# martix_connect_2.net
KiCad netlist of a schematic drawn in Altium Designer
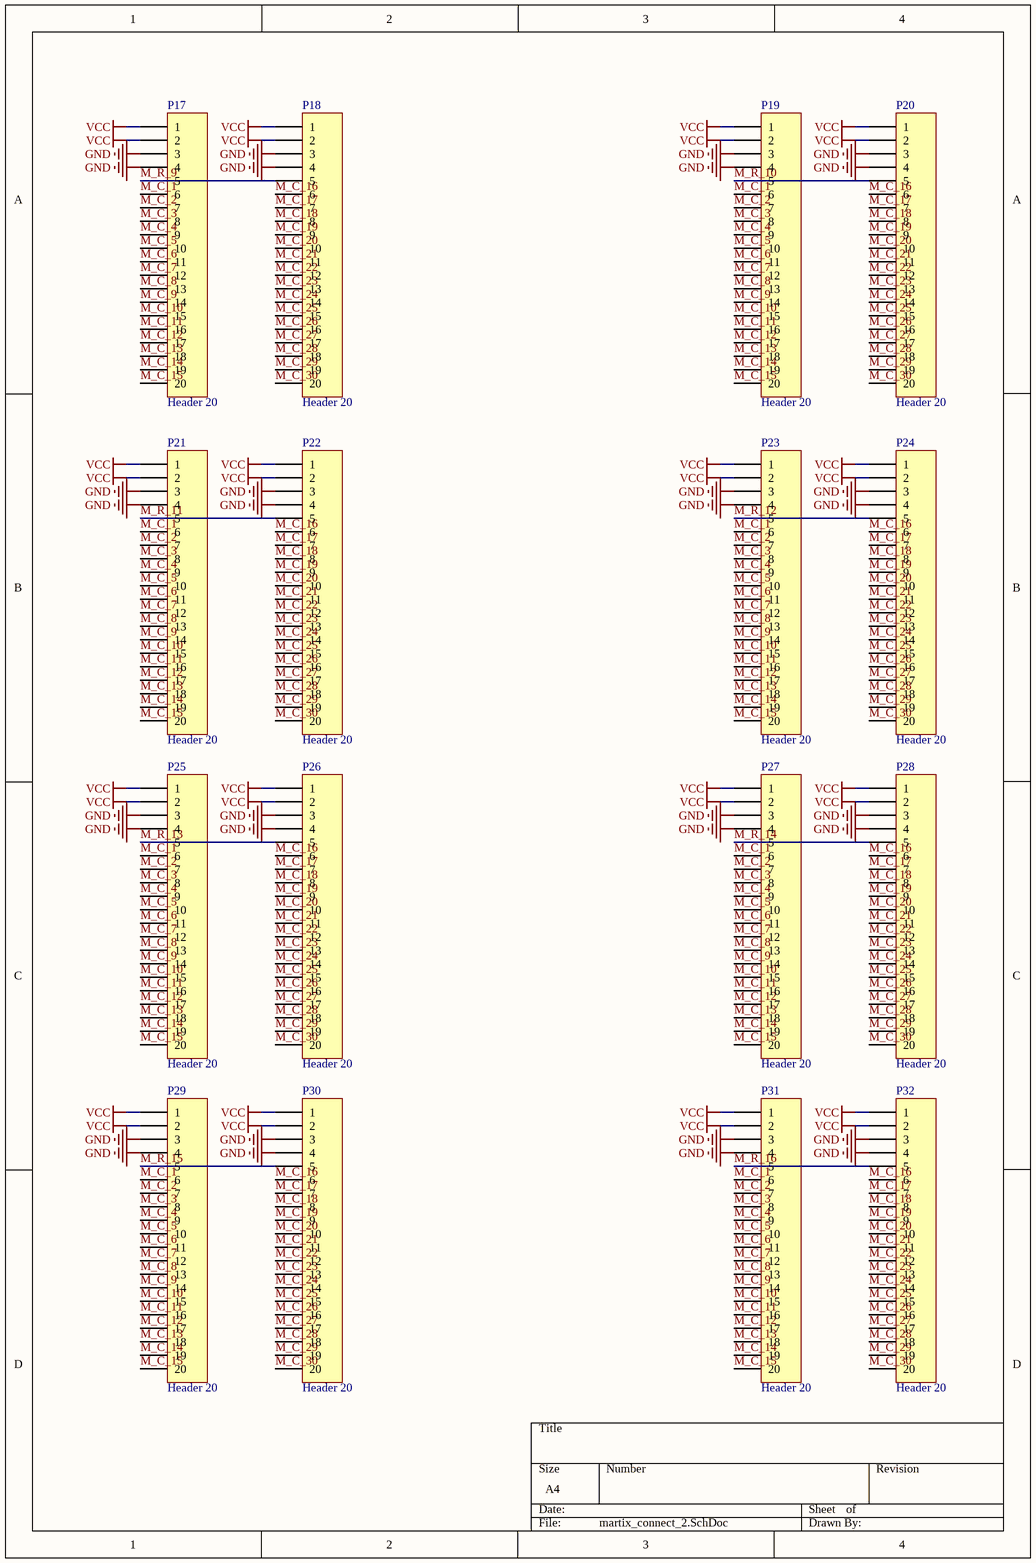
[diagram p0: martix_connect_2.SchDoc]

(export (version "E")
  (design (tool "Eeschema 10.0.6"))
  (components
    (comp (ref "P17")
      (value "Header 20")
      (footprint "FPC0.5 2H-WS-20P")
      (description "Header, 20-Pin")
      (fields (field (name "PUBLISHER") "Altium Limited"))
      (libsource (lib "Miscellaneous Connectors") (part "Header 20"))
    )
    (comp (ref "P18")
      (value "Header 20")
      (footprint "FPC0.5 2H-WS-20P")
      (description "Header, 20-Pin")
      (fields (field (name "PUBLISHER") "Altium Limited"))
      (libsource (lib "Miscellaneous Connectors") (part "Header 20"))
    )
    (comp (ref "P19")
      (value "Header 20")
      (footprint "FPC0.5 2H-WS-20P")
      (description "Header, 20-Pin")
      (fields (field (name "PUBLISHER") "Altium Limited"))
      (libsource (lib "Miscellaneous Connectors") (part "Header 20"))
    )
    (comp (ref "P20")
      (value "Header 20")
      (footprint "FPC0.5 2H-WS-20P")
      (description "Header, 20-Pin")
      (fields (field (name "PUBLISHER") "Altium Limited"))
      (libsource (lib "Miscellaneous Connectors") (part "Header 20"))
    )
    (comp (ref "P21")
      (value "Header 20")
      (footprint "FPC0.5 2H-WS-20P")
      (description "Header, 20-Pin")
      (fields (field (name "PUBLISHER") "Altium Limited"))
      (libsource (lib "Miscellaneous Connectors") (part "Header 20"))
    )
    (comp (ref "P22")
      (value "Header 20")
      (footprint "FPC0.5 2H-WS-20P")
      (description "Header, 20-Pin")
      (fields (field (name "PUBLISHER") "Altium Limited"))
      (libsource (lib "Miscellaneous Connectors") (part "Header 20"))
    )
    (comp (ref "P23")
      (value "Header 20")
      (footprint "FPC0.5 2H-WS-20P")
      (description "Header, 20-Pin")
      (fields (field (name "PUBLISHER") "Altium Limited"))
      (libsource (lib "Miscellaneous Connectors") (part "Header 20"))
    )
    (comp (ref "P24")
      (value "Header 20")
      (footprint "FPC0.5 2H-WS-20P")
      (description "Header, 20-Pin")
      (fields (field (name "PUBLISHER") "Altium Limited"))
      (libsource (lib "Miscellaneous Connectors") (part "Header 20"))
    )
    (comp (ref "P25")
      (value "Header 20")
      (footprint "FPC0.5 2H-WS-20P")
      (description "Header, 20-Pin")
      (fields (field (name "PUBLISHER") "Altium Limited"))
      (libsource (lib "Miscellaneous Connectors") (part "Header 20"))
    )
    (comp (ref "P26")
      (value "Header 20")
      (footprint "FPC0.5 2H-WS-20P")
      (description "Header, 20-Pin")
      (fields (field (name "PUBLISHER") "Altium Limited"))
      (libsource (lib "Miscellaneous Connectors") (part "Header 20"))
    )
    (comp (ref "P27")
      (value "Header 20")
      (footprint "FPC0.5 2H-WS-20P")
      (description "Header, 20-Pin")
      (fields (field (name "PUBLISHER") "Altium Limited"))
      (libsource (lib "Miscellaneous Connectors") (part "Header 20"))
    )
    (comp (ref "P28")
      (value "Header 20")
      (footprint "FPC0.5 2H-WS-20P")
      (description "Header, 20-Pin")
      (fields (field (name "PUBLISHER") "Altium Limited"))
      (libsource (lib "Miscellaneous Connectors") (part "Header 20"))
    )
    (comp (ref "P29")
      (value "Header 20")
      (footprint "FPC0.5 2H-WS-20P")
      (description "Header, 20-Pin")
      (fields (field (name "PUBLISHER") "Altium Limited"))
      (libsource (lib "Miscellaneous Connectors") (part "Header 20"))
    )
    (comp (ref "P30")
      (value "Header 20")
      (footprint "FPC0.5 2H-WS-20P")
      (description "Header, 20-Pin")
      (fields (field (name "PUBLISHER") "Altium Limited"))
      (libsource (lib "Miscellaneous Connectors") (part "Header 20"))
    )
    (comp (ref "P31")
      (value "Header 20")
      (footprint "FPC0.5 2H-WS-20P")
      (description "Header, 20-Pin")
      (fields (field (name "PUBLISHER") "Altium Limited"))
      (libsource (lib "Miscellaneous Connectors") (part "Header 20"))
    )
    (comp (ref "P32")
      (value "Header 20")
      (footprint "FPC0.5 2H-WS-20P")
      (description "Header, 20-Pin")
      (fields (field (name "PUBLISHER") "Altium Limited"))
      (libsource (lib "Miscellaneous Connectors") (part "Header 20"))
    )
  )
  (nets
    (net (code "1") (name "/M_C_1") (class "Default")
      (node (ref "P17") (pin "6") (pinfunction "6_6") (pintype "passive"))
      (node (ref "P19") (pin "6") (pinfunction "6_6") (pintype "passive"))
      (node (ref "P21") (pin "6") (pinfunction "6_6") (pintype "passive"))
      (node (ref "P23") (pin "6") (pinfunction "6_6") (pintype "passive"))
      (node (ref "P25") (pin "6") (pinfunction "6_6") (pintype "passive"))
      (node (ref "P27") (pin "6") (pinfunction "6_6") (pintype "passive"))
      (node (ref "P29") (pin "6") (pinfunction "6_6") (pintype "passive"))
      (node (ref "P31") (pin "6") (pinfunction "6_6") (pintype "passive"))
    )
    (net (code "2") (name "/M_C_2") (class "Default")
      (node (ref "P17") (pin "7") (pinfunction "7_7") (pintype "passive"))
      (node (ref "P19") (pin "7") (pinfunction "7_7") (pintype "passive"))
      (node (ref "P21") (pin "7") (pinfunction "7_7") (pintype "passive"))
      (node (ref "P23") (pin "7") (pinfunction "7_7") (pintype "passive"))
      (node (ref "P25") (pin "7") (pinfunction "7_7") (pintype "passive"))
      (node (ref "P27") (pin "7") (pinfunction "7_7") (pintype "passive"))
      (node (ref "P29") (pin "7") (pinfunction "7_7") (pintype "passive"))
      (node (ref "P31") (pin "7") (pinfunction "7_7") (pintype "passive"))
    )
    (net (code "3") (name "/M_C_3") (class "Default")
      (node (ref "P17") (pin "8") (pinfunction "8_8") (pintype "passive"))
      (node (ref "P19") (pin "8") (pinfunction "8_8") (pintype "passive"))
      (node (ref "P21") (pin "8") (pinfunction "8_8") (pintype "passive"))
      (node (ref "P23") (pin "8") (pinfunction "8_8") (pintype "passive"))
      (node (ref "P25") (pin "8") (pinfunction "8_8") (pintype "passive"))
      (node (ref "P27") (pin "8") (pinfunction "8_8") (pintype "passive"))
      (node (ref "P29") (pin "8") (pinfunction "8_8") (pintype "passive"))
      (node (ref "P31") (pin "8") (pinfunction "8_8") (pintype "passive"))
    )
    (net (code "4") (name "/M_C_4") (class "Default")
      (node (ref "P17") (pin "9") (pinfunction "9_9") (pintype "passive"))
      (node (ref "P19") (pin "9") (pinfunction "9_9") (pintype "passive"))
      (node (ref "P21") (pin "9") (pinfunction "9_9") (pintype "passive"))
      (node (ref "P23") (pin "9") (pinfunction "9_9") (pintype "passive"))
      (node (ref "P25") (pin "9") (pinfunction "9_9") (pintype "passive"))
      (node (ref "P27") (pin "9") (pinfunction "9_9") (pintype "passive"))
      (node (ref "P29") (pin "9") (pinfunction "9_9") (pintype "passive"))
      (node (ref "P31") (pin "9") (pinfunction "9_9") (pintype "passive"))
    )
    (net (code "5") (name "/M_C_5") (class "Default")
      (node (ref "P17") (pin "10") (pinfunction "10_10") (pintype "passive"))
      (node (ref "P19") (pin "10") (pinfunction "10_10") (pintype "passive"))
      (node (ref "P21") (pin "10") (pinfunction "10_10") (pintype "passive"))
      (node (ref "P23") (pin "10") (pinfunction "10_10") (pintype "passive"))
      (node (ref "P25") (pin "10") (pinfunction "10_10") (pintype "passive"))
      (node (ref "P27") (pin "10") (pinfunction "10_10") (pintype "passive"))
      (node (ref "P29") (pin "10") (pinfunction "10_10") (pintype "passive"))
      (node (ref "P31") (pin "10") (pinfunction "10_10") (pintype "passive"))
    )
    (net (code "6") (name "/M_C_6") (class "Default")
      (node (ref "P17") (pin "11") (pinfunction "11_11") (pintype "passive"))
      (node (ref "P19") (pin "11") (pinfunction "11_11") (pintype "passive"))
      (node (ref "P21") (pin "11") (pinfunction "11_11") (pintype "passive"))
      (node (ref "P23") (pin "11") (pinfunction "11_11") (pintype "passive"))
      (node (ref "P25") (pin "11") (pinfunction "11_11") (pintype "passive"))
      (node (ref "P27") (pin "11") (pinfunction "11_11") (pintype "passive"))
      (node (ref "P29") (pin "11") (pinfunction "11_11") (pintype "passive"))
      (node (ref "P31") (pin "11") (pinfunction "11_11") (pintype "passive"))
    )
    (net (code "7") (name "/M_C_7") (class "Default")
      (node (ref "P17") (pin "12") (pinfunction "12_12") (pintype "passive"))
      (node (ref "P19") (pin "12") (pinfunction "12_12") (pintype "passive"))
      (node (ref "P21") (pin "12") (pinfunction "12_12") (pintype "passive"))
      (node (ref "P23") (pin "12") (pinfunction "12_12") (pintype "passive"))
      (node (ref "P25") (pin "12") (pinfunction "12_12") (pintype "passive"))
      (node (ref "P27") (pin "12") (pinfunction "12_12") (pintype "passive"))
      (node (ref "P29") (pin "12") (pinfunction "12_12") (pintype "passive"))
      (node (ref "P31") (pin "12") (pinfunction "12_12") (pintype "passive"))
    )
    (net (code "8") (name "/M_C_8") (class "Default")
      (node (ref "P17") (pin "13") (pinfunction "13_13") (pintype "passive"))
      (node (ref "P19") (pin "13") (pinfunction "13_13") (pintype "passive"))
      (node (ref "P21") (pin "13") (pinfunction "13_13") (pintype "passive"))
      (node (ref "P23") (pin "13") (pinfunction "13_13") (pintype "passive"))
      (node (ref "P25") (pin "13") (pinfunction "13_13") (pintype "passive"))
      (node (ref "P27") (pin "13") (pinfunction "13_13") (pintype "passive"))
      (node (ref "P29") (pin "13") (pinfunction "13_13") (pintype "passive"))
      (node (ref "P31") (pin "13") (pinfunction "13_13") (pintype "passive"))
    )
    (net (code "9") (name "/M_C_9") (class "Default")
      (node (ref "P17") (pin "14") (pinfunction "14_14") (pintype "passive"))
      (node (ref "P19") (pin "14") (pinfunction "14_14") (pintype "passive"))
      (node (ref "P21") (pin "14") (pinfunction "14_14") (pintype "passive"))
      (node (ref "P23") (pin "14") (pinfunction "14_14") (pintype "passive"))
      (node (ref "P25") (pin "14") (pinfunction "14_14") (pintype "passive"))
      (node (ref "P27") (pin "14") (pinfunction "14_14") (pintype "passive"))
      (node (ref "P29") (pin "14") (pinfunction "14_14") (pintype "passive"))
      (node (ref "P31") (pin "14") (pinfunction "14_14") (pintype "passive"))
    )
    (net (code "10") (name "/M_C_10") (class "Default")
      (node (ref "P17") (pin "15") (pinfunction "15_15") (pintype "passive"))
      (node (ref "P19") (pin "15") (pinfunction "15_15") (pintype "passive"))
      (node (ref "P21") (pin "15") (pinfunction "15_15") (pintype "passive"))
      (node (ref "P23") (pin "15") (pinfunction "15_15") (pintype "passive"))
      (node (ref "P25") (pin "15") (pinfunction "15_15") (pintype "passive"))
      (node (ref "P27") (pin "15") (pinfunction "15_15") (pintype "passive"))
      (node (ref "P29") (pin "15") (pinfunction "15_15") (pintype "passive"))
      (node (ref "P31") (pin "15") (pinfunction "15_15") (pintype "passive"))
    )
    (net (code "11") (name "/M_C_11") (class "Default")
      (node (ref "P17") (pin "16") (pinfunction "16_16") (pintype "passive"))
      (node (ref "P19") (pin "16") (pinfunction "16_16") (pintype "passive"))
      (node (ref "P21") (pin "16") (pinfunction "16_16") (pintype "passive"))
      (node (ref "P23") (pin "16") (pinfunction "16_16") (pintype "passive"))
      (node (ref "P25") (pin "16") (pinfunction "16_16") (pintype "passive"))
      (node (ref "P27") (pin "16") (pinfunction "16_16") (pintype "passive"))
      (node (ref "P29") (pin "16") (pinfunction "16_16") (pintype "passive"))
      (node (ref "P31") (pin "16") (pinfunction "16_16") (pintype "passive"))
    )
    (net (code "12") (name "/M_C_12") (class "Default")
      (node (ref "P17") (pin "17") (pinfunction "17_17") (pintype "passive"))
      (node (ref "P19") (pin "17") (pinfunction "17_17") (pintype "passive"))
      (node (ref "P21") (pin "17") (pinfunction "17_17") (pintype "passive"))
      (node (ref "P23") (pin "17") (pinfunction "17_17") (pintype "passive"))
      (node (ref "P25") (pin "17") (pinfunction "17_17") (pintype "passive"))
      (node (ref "P27") (pin "17") (pinfunction "17_17") (pintype "passive"))
      (node (ref "P29") (pin "17") (pinfunction "17_17") (pintype "passive"))
      (node (ref "P31") (pin "17") (pinfunction "17_17") (pintype "passive"))
    )
    (net (code "13") (name "/M_C_13") (class "Default")
      (node (ref "P17") (pin "18") (pinfunction "18_18") (pintype "passive"))
      (node (ref "P19") (pin "18") (pinfunction "18_18") (pintype "passive"))
      (node (ref "P21") (pin "18") (pinfunction "18_18") (pintype "passive"))
      (node (ref "P23") (pin "18") (pinfunction "18_18") (pintype "passive"))
      (node (ref "P25") (pin "18") (pinfunction "18_18") (pintype "passive"))
      (node (ref "P27") (pin "18") (pinfunction "18_18") (pintype "passive"))
      (node (ref "P29") (pin "18") (pinfunction "18_18") (pintype "passive"))
      (node (ref "P31") (pin "18") (pinfunction "18_18") (pintype "passive"))
    )
    (net (code "14") (name "/M_C_14") (class "Default")
      (node (ref "P17") (pin "19") (pinfunction "19_19") (pintype "passive"))
      (node (ref "P19") (pin "19") (pinfunction "19_19") (pintype "passive"))
      (node (ref "P21") (pin "19") (pinfunction "19_19") (pintype "passive"))
      (node (ref "P23") (pin "19") (pinfunction "19_19") (pintype "passive"))
      (node (ref "P25") (pin "19") (pinfunction "19_19") (pintype "passive"))
      (node (ref "P27") (pin "19") (pinfunction "19_19") (pintype "passive"))
      (node (ref "P29") (pin "19") (pinfunction "19_19") (pintype "passive"))
      (node (ref "P31") (pin "19") (pinfunction "19_19") (pintype "passive"))
    )
    (net (code "15") (name "/M_C_15") (class "Default")
      (node (ref "P17") (pin "20") (pinfunction "20_20") (pintype "passive"))
      (node (ref "P19") (pin "20") (pinfunction "20_20") (pintype "passive"))
      (node (ref "P21") (pin "20") (pinfunction "20_20") (pintype "passive"))
      (node (ref "P23") (pin "20") (pinfunction "20_20") (pintype "passive"))
      (node (ref "P25") (pin "20") (pinfunction "20_20") (pintype "passive"))
      (node (ref "P27") (pin "20") (pinfunction "20_20") (pintype "passive"))
      (node (ref "P29") (pin "20") (pinfunction "20_20") (pintype "passive"))
      (node (ref "P31") (pin "20") (pinfunction "20_20") (pintype "passive"))
    )
    (net (code "16") (name "/M_C_16") (class "Default")
      (node (ref "P18") (pin "6") (pinfunction "6_6") (pintype "passive"))
      (node (ref "P20") (pin "6") (pinfunction "6_6") (pintype "passive"))
      (node (ref "P22") (pin "6") (pinfunction "6_6") (pintype "passive"))
      (node (ref "P24") (pin "6") (pinfunction "6_6") (pintype "passive"))
      (node (ref "P26") (pin "6") (pinfunction "6_6") (pintype "passive"))
      (node (ref "P28") (pin "6") (pinfunction "6_6") (pintype "passive"))
      (node (ref "P30") (pin "6") (pinfunction "6_6") (pintype "passive"))
      (node (ref "P32") (pin "6") (pinfunction "6_6") (pintype "passive"))
    )
    (net (code "17") (name "/M_C_17") (class "Default")
      (node (ref "P18") (pin "7") (pinfunction "7_7") (pintype "passive"))
      (node (ref "P20") (pin "7") (pinfunction "7_7") (pintype "passive"))
      (node (ref "P22") (pin "7") (pinfunction "7_7") (pintype "passive"))
      (node (ref "P24") (pin "7") (pinfunction "7_7") (pintype "passive"))
      (node (ref "P26") (pin "7") (pinfunction "7_7") (pintype "passive"))
      (node (ref "P28") (pin "7") (pinfunction "7_7") (pintype "passive"))
      (node (ref "P30") (pin "7") (pinfunction "7_7") (pintype "passive"))
      (node (ref "P32") (pin "7") (pinfunction "7_7") (pintype "passive"))
    )
    (net (code "18") (name "/M_C_18") (class "Default")
      (node (ref "P18") (pin "8") (pinfunction "8_8") (pintype "passive"))
      (node (ref "P20") (pin "8") (pinfunction "8_8") (pintype "passive"))
      (node (ref "P22") (pin "8") (pinfunction "8_8") (pintype "passive"))
      (node (ref "P24") (pin "8") (pinfunction "8_8") (pintype "passive"))
      (node (ref "P26") (pin "8") (pinfunction "8_8") (pintype "passive"))
      (node (ref "P28") (pin "8") (pinfunction "8_8") (pintype "passive"))
      (node (ref "P30") (pin "8") (pinfunction "8_8") (pintype "passive"))
      (node (ref "P32") (pin "8") (pinfunction "8_8") (pintype "passive"))
    )
    (net (code "19") (name "/M_C_19") (class "Default")
      (node (ref "P18") (pin "9") (pinfunction "9_9") (pintype "passive"))
      (node (ref "P20") (pin "9") (pinfunction "9_9") (pintype "passive"))
      (node (ref "P22") (pin "9") (pinfunction "9_9") (pintype "passive"))
      (node (ref "P24") (pin "9") (pinfunction "9_9") (pintype "passive"))
      (node (ref "P26") (pin "9") (pinfunction "9_9") (pintype "passive"))
      (node (ref "P28") (pin "9") (pinfunction "9_9") (pintype "passive"))
      (node (ref "P30") (pin "9") (pinfunction "9_9") (pintype "passive"))
      (node (ref "P32") (pin "9") (pinfunction "9_9") (pintype "passive"))
    )
    (net (code "20") (name "/M_C_20") (class "Default")
      (node (ref "P18") (pin "10") (pinfunction "10_10") (pintype "passive"))
      (node (ref "P20") (pin "10") (pinfunction "10_10") (pintype "passive"))
      (node (ref "P22") (pin "10") (pinfunction "10_10") (pintype "passive"))
      (node (ref "P24") (pin "10") (pinfunction "10_10") (pintype "passive"))
      (node (ref "P26") (pin "10") (pinfunction "10_10") (pintype "passive"))
      (node (ref "P28") (pin "10") (pinfunction "10_10") (pintype "passive"))
      (node (ref "P30") (pin "10") (pinfunction "10_10") (pintype "passive"))
      (node (ref "P32") (pin "10") (pinfunction "10_10") (pintype "passive"))
    )
    (net (code "21") (name "/M_C_21") (class "Default")
      (node (ref "P18") (pin "11") (pinfunction "11_11") (pintype "passive"))
      (node (ref "P20") (pin "11") (pinfunction "11_11") (pintype "passive"))
      (node (ref "P22") (pin "11") (pinfunction "11_11") (pintype "passive"))
      (node (ref "P24") (pin "11") (pinfunction "11_11") (pintype "passive"))
      (node (ref "P26") (pin "11") (pinfunction "11_11") (pintype "passive"))
      (node (ref "P28") (pin "11") (pinfunction "11_11") (pintype "passive"))
      (node (ref "P30") (pin "11") (pinfunction "11_11") (pintype "passive"))
      (node (ref "P32") (pin "11") (pinfunction "11_11") (pintype "passive"))
    )
    (net (code "22") (name "/M_C_22") (class "Default")
      (node (ref "P18") (pin "12") (pinfunction "12_12") (pintype "passive"))
      (node (ref "P20") (pin "12") (pinfunction "12_12") (pintype "passive"))
      (node (ref "P22") (pin "12") (pinfunction "12_12") (pintype "passive"))
      (node (ref "P24") (pin "12") (pinfunction "12_12") (pintype "passive"))
      (node (ref "P26") (pin "12") (pinfunction "12_12") (pintype "passive"))
      (node (ref "P28") (pin "12") (pinfunction "12_12") (pintype "passive"))
      (node (ref "P30") (pin "12") (pinfunction "12_12") (pintype "passive"))
      (node (ref "P32") (pin "12") (pinfunction "12_12") (pintype "passive"))
    )
    (net (code "23") (name "/M_C_23") (class "Default")
      (node (ref "P18") (pin "13") (pinfunction "13_13") (pintype "passive"))
      (node (ref "P20") (pin "13") (pinfunction "13_13") (pintype "passive"))
      (node (ref "P22") (pin "13") (pinfunction "13_13") (pintype "passive"))
      (node (ref "P24") (pin "13") (pinfunction "13_13") (pintype "passive"))
      (node (ref "P26") (pin "13") (pinfunction "13_13") (pintype "passive"))
      (node (ref "P28") (pin "13") (pinfunction "13_13") (pintype "passive"))
      (node (ref "P30") (pin "13") (pinfunction "13_13") (pintype "passive"))
      (node (ref "P32") (pin "13") (pinfunction "13_13") (pintype "passive"))
    )
    (net (code "24") (name "/M_C_24") (class "Default")
      (node (ref "P18") (pin "14") (pinfunction "14_14") (pintype "passive"))
      (node (ref "P20") (pin "14") (pinfunction "14_14") (pintype "passive"))
      (node (ref "P22") (pin "14") (pinfunction "14_14") (pintype "passive"))
      (node (ref "P24") (pin "14") (pinfunction "14_14") (pintype "passive"))
      (node (ref "P26") (pin "14") (pinfunction "14_14") (pintype "passive"))
      (node (ref "P28") (pin "14") (pinfunction "14_14") (pintype "passive"))
      (node (ref "P30") (pin "14") (pinfunction "14_14") (pintype "passive"))
      (node (ref "P32") (pin "14") (pinfunction "14_14") (pintype "passive"))
    )
    (net (code "25") (name "/M_C_25") (class "Default")
      (node (ref "P18") (pin "15") (pinfunction "15_15") (pintype "passive"))
      (node (ref "P20") (pin "15") (pinfunction "15_15") (pintype "passive"))
      (node (ref "P22") (pin "15") (pinfunction "15_15") (pintype "passive"))
      (node (ref "P24") (pin "15") (pinfunction "15_15") (pintype "passive"))
      (node (ref "P26") (pin "15") (pinfunction "15_15") (pintype "passive"))
      (node (ref "P28") (pin "15") (pinfunction "15_15") (pintype "passive"))
      (node (ref "P30") (pin "15") (pinfunction "15_15") (pintype "passive"))
      (node (ref "P32") (pin "15") (pinfunction "15_15") (pintype "passive"))
    )
    (net (code "26") (name "/M_C_26") (class "Default")
      (node (ref "P18") (pin "16") (pinfunction "16_16") (pintype "passive"))
      (node (ref "P20") (pin "16") (pinfunction "16_16") (pintype "passive"))
      (node (ref "P22") (pin "16") (pinfunction "16_16") (pintype "passive"))
      (node (ref "P24") (pin "16") (pinfunction "16_16") (pintype "passive"))
      (node (ref "P26") (pin "16") (pinfunction "16_16") (pintype "passive"))
      (node (ref "P28") (pin "16") (pinfunction "16_16") (pintype "passive"))
      (node (ref "P30") (pin "16") (pinfunction "16_16") (pintype "passive"))
      (node (ref "P32") (pin "16") (pinfunction "16_16") (pintype "passive"))
    )
    (net (code "27") (name "/M_C_27") (class "Default")
      (node (ref "P18") (pin "17") (pinfunction "17_17") (pintype "passive"))
      (node (ref "P20") (pin "17") (pinfunction "17_17") (pintype "passive"))
      (node (ref "P22") (pin "17") (pinfunction "17_17") (pintype "passive"))
      (node (ref "P24") (pin "17") (pinfunction "17_17") (pintype "passive"))
      (node (ref "P26") (pin "17") (pinfunction "17_17") (pintype "passive"))
      (node (ref "P28") (pin "17") (pinfunction "17_17") (pintype "passive"))
      (node (ref "P30") (pin "17") (pinfunction "17_17") (pintype "passive"))
      (node (ref "P32") (pin "17") (pinfunction "17_17") (pintype "passive"))
    )
    (net (code "28") (name "/M_C_28") (class "Default")
      (node (ref "P18") (pin "18") (pinfunction "18_18") (pintype "passive"))
      (node (ref "P20") (pin "18") (pinfunction "18_18") (pintype "passive"))
      (node (ref "P22") (pin "18") (pinfunction "18_18") (pintype "passive"))
      (node (ref "P24") (pin "18") (pinfunction "18_18") (pintype "passive"))
      (node (ref "P26") (pin "18") (pinfunction "18_18") (pintype "passive"))
      (node (ref "P28") (pin "18") (pinfunction "18_18") (pintype "passive"))
      (node (ref "P30") (pin "18") (pinfunction "18_18") (pintype "passive"))
      (node (ref "P32") (pin "18") (pinfunction "18_18") (pintype "passive"))
    )
    (net (code "29") (name "/M_C_29") (class "Default")
      (node (ref "P18") (pin "19") (pinfunction "19_19") (pintype "passive"))
      (node (ref "P20") (pin "19") (pinfunction "19_19") (pintype "passive"))
      (node (ref "P22") (pin "19") (pinfunction "19_19") (pintype "passive"))
      (node (ref "P24") (pin "19") (pinfunction "19_19") (pintype "passive"))
      (node (ref "P26") (pin "19") (pinfunction "19_19") (pintype "passive"))
      (node (ref "P28") (pin "19") (pinfunction "19_19") (pintype "passive"))
      (node (ref "P30") (pin "19") (pinfunction "19_19") (pintype "passive"))
      (node (ref "P32") (pin "19") (pinfunction "19_19") (pintype "passive"))
    )
    (net (code "30") (name "/M_C_30") (class "Default")
      (node (ref "P18") (pin "20") (pinfunction "20_20") (pintype "passive"))
      (node (ref "P20") (pin "20") (pinfunction "20_20") (pintype "passive"))
      (node (ref "P22") (pin "20") (pinfunction "20_20") (pintype "passive"))
      (node (ref "P24") (pin "20") (pinfunction "20_20") (pintype "passive"))
      (node (ref "P26") (pin "20") (pinfunction "20_20") (pintype "passive"))
      (node (ref "P28") (pin "20") (pinfunction "20_20") (pintype "passive"))
      (node (ref "P30") (pin "20") (pinfunction "20_20") (pintype "passive"))
      (node (ref "P32") (pin "20") (pinfunction "20_20") (pintype "passive"))
    )
    (net (code "31") (name "/M_R_9") (class "Default")
      (node (ref "P17") (pin "5") (pinfunction "5_5") (pintype "passive"))
      (node (ref "P18") (pin "5") (pinfunction "5_5") (pintype "passive"))
    )
    (net (code "32") (name "/M_R_10") (class "Default")
      (node (ref "P19") (pin "5") (pinfunction "5_5") (pintype "passive"))
      (node (ref "P20") (pin "5") (pinfunction "5_5") (pintype "passive"))
    )
    (net (code "33") (name "/M_R_11") (class "Default")
      (node (ref "P21") (pin "5") (pinfunction "5_5") (pintype "passive"))
      (node (ref "P22") (pin "5") (pinfunction "5_5") (pintype "passive"))
    )
    (net (code "34") (name "/M_R_12") (class "Default")
      (node (ref "P23") (pin "5") (pinfunction "5_5") (pintype "passive"))
      (node (ref "P24") (pin "5") (pinfunction "5_5") (pintype "passive"))
    )
    (net (code "35") (name "/M_R_13") (class "Default")
      (node (ref "P25") (pin "5") (pinfunction "5_5") (pintype "passive"))
      (node (ref "P26") (pin "5") (pinfunction "5_5") (pintype "passive"))
    )
    (net (code "36") (name "/M_R_14") (class "Default")
      (node (ref "P27") (pin "5") (pinfunction "5_5") (pintype "passive"))
      (node (ref "P28") (pin "5") (pinfunction "5_5") (pintype "passive"))
    )
    (net (code "37") (name "/M_R_15") (class "Default")
      (node (ref "P29") (pin "5") (pinfunction "5_5") (pintype "passive"))
      (node (ref "P30") (pin "5") (pinfunction "5_5") (pintype "passive"))
    )
    (net (code "38") (name "/M_R_16") (class "Default")
      (node (ref "P31") (pin "5") (pinfunction "5_5") (pintype "passive"))
      (node (ref "P32") (pin "5") (pinfunction "5_5") (pintype "passive"))
    )
    (net (code "39") (name "GND") (class "Default")
      (node (ref "P17") (pin "3") (pinfunction "3_3") (pintype "passive"))
      (node (ref "P17") (pin "4") (pinfunction "4_4") (pintype "passive"))
      (node (ref "P18") (pin "3") (pinfunction "3_3") (pintype "passive"))
      (node (ref "P18") (pin "4") (pinfunction "4_4") (pintype "passive"))
      (node (ref "P19") (pin "3") (pinfunction "3_3") (pintype "passive"))
      (node (ref "P19") (pin "4") (pinfunction "4_4") (pintype "passive"))
      (node (ref "P20") (pin "3") (pinfunction "3_3") (pintype "passive"))
      (node (ref "P20") (pin "4") (pinfunction "4_4") (pintype "passive"))
      (node (ref "P21") (pin "3") (pinfunction "3_3") (pintype "passive"))
      (node (ref "P21") (pin "4") (pinfunction "4_4") (pintype "passive"))
      (node (ref "P22") (pin "3") (pinfunction "3_3") (pintype "passive"))
      (node (ref "P22") (pin "4") (pinfunction "4_4") (pintype "passive"))
      (node (ref "P23") (pin "3") (pinfunction "3_3") (pintype "passive"))
      (node (ref "P23") (pin "4") (pinfunction "4_4") (pintype "passive"))
      (node (ref "P24") (pin "3") (pinfunction "3_3") (pintype "passive"))
      (node (ref "P24") (pin "4") (pinfunction "4_4") (pintype "passive"))
      (node (ref "P25") (pin "3") (pinfunction "3_3") (pintype "passive"))
      (node (ref "P25") (pin "4") (pinfunction "4_4") (pintype "passive"))
      (node (ref "P26") (pin "3") (pinfunction "3_3") (pintype "passive"))
      (node (ref "P26") (pin "4") (pinfunction "4_4") (pintype "passive"))
      (node (ref "P27") (pin "3") (pinfunction "3_3") (pintype "passive"))
      (node (ref "P27") (pin "4") (pinfunction "4_4") (pintype "passive"))
      (node (ref "P28") (pin "3") (pinfunction "3_3") (pintype "passive"))
      (node (ref "P28") (pin "4") (pinfunction "4_4") (pintype "passive"))
      (node (ref "P29") (pin "3") (pinfunction "3_3") (pintype "passive"))
      (node (ref "P29") (pin "4") (pinfunction "4_4") (pintype "passive"))
      (node (ref "P30") (pin "3") (pinfunction "3_3") (pintype "passive"))
      (node (ref "P30") (pin "4") (pinfunction "4_4") (pintype "passive"))
      (node (ref "P31") (pin "3") (pinfunction "3_3") (pintype "passive"))
      (node (ref "P31") (pin "4") (pinfunction "4_4") (pintype "passive"))
      (node (ref "P32") (pin "3") (pinfunction "3_3") (pintype "passive"))
      (node (ref "P32") (pin "4") (pinfunction "4_4") (pintype "passive"))
    )
    (net (code "40") (name "VCC") (class "Default")
      (node (ref "P17") (pin "1") (pinfunction "1_1") (pintype "passive"))
      (node (ref "P17") (pin "2") (pinfunction "2_2") (pintype "passive"))
      (node (ref "P18") (pin "1") (pinfunction "1_1") (pintype "passive"))
      (node (ref "P18") (pin "2") (pinfunction "2_2") (pintype "passive"))
      (node (ref "P19") (pin "1") (pinfunction "1_1") (pintype "passive"))
      (node (ref "P19") (pin "2") (pinfunction "2_2") (pintype "passive"))
      (node (ref "P20") (pin "1") (pinfunction "1_1") (pintype "passive"))
      (node (ref "P20") (pin "2") (pinfunction "2_2") (pintype "passive"))
      (node (ref "P21") (pin "1") (pinfunction "1_1") (pintype "passive"))
      (node (ref "P21") (pin "2") (pinfunction "2_2") (pintype "passive"))
      (node (ref "P22") (pin "1") (pinfunction "1_1") (pintype "passive"))
      (node (ref "P22") (pin "2") (pinfunction "2_2") (pintype "passive"))
      (node (ref "P23") (pin "1") (pinfunction "1_1") (pintype "passive"))
      (node (ref "P23") (pin "2") (pinfunction "2_2") (pintype "passive"))
      (node (ref "P24") (pin "1") (pinfunction "1_1") (pintype "passive"))
      (node (ref "P24") (pin "2") (pinfunction "2_2") (pintype "passive"))
      (node (ref "P25") (pin "1") (pinfunction "1_1") (pintype "passive"))
      (node (ref "P25") (pin "2") (pinfunction "2_2") (pintype "passive"))
      (node (ref "P26") (pin "1") (pinfunction "1_1") (pintype "passive"))
      (node (ref "P26") (pin "2") (pinfunction "2_2") (pintype "passive"))
      (node (ref "P27") (pin "1") (pinfunction "1_1") (pintype "passive"))
      (node (ref "P27") (pin "2") (pinfunction "2_2") (pintype "passive"))
      (node (ref "P28") (pin "1") (pinfunction "1_1") (pintype "passive"))
      (node (ref "P28") (pin "2") (pinfunction "2_2") (pintype "passive"))
      (node (ref "P29") (pin "1") (pinfunction "1_1") (pintype "passive"))
      (node (ref "P29") (pin "2") (pinfunction "2_2") (pintype "passive"))
      (node (ref "P30") (pin "1") (pinfunction "1_1") (pintype "passive"))
      (node (ref "P30") (pin "2") (pinfunction "2_2") (pintype "passive"))
      (node (ref "P31") (pin "1") (pinfunction "1_1") (pintype "passive"))
      (node (ref "P31") (pin "2") (pinfunction "2_2") (pintype "passive"))
      (node (ref "P32") (pin "1") (pinfunction "1_1") (pintype "passive"))
      (node (ref "P32") (pin "2") (pinfunction "2_2") (pintype "passive"))
    )
  )
)
